# IO_BOARD_TOP.net
KiCad netlist of a schematic drawn in EAGLE
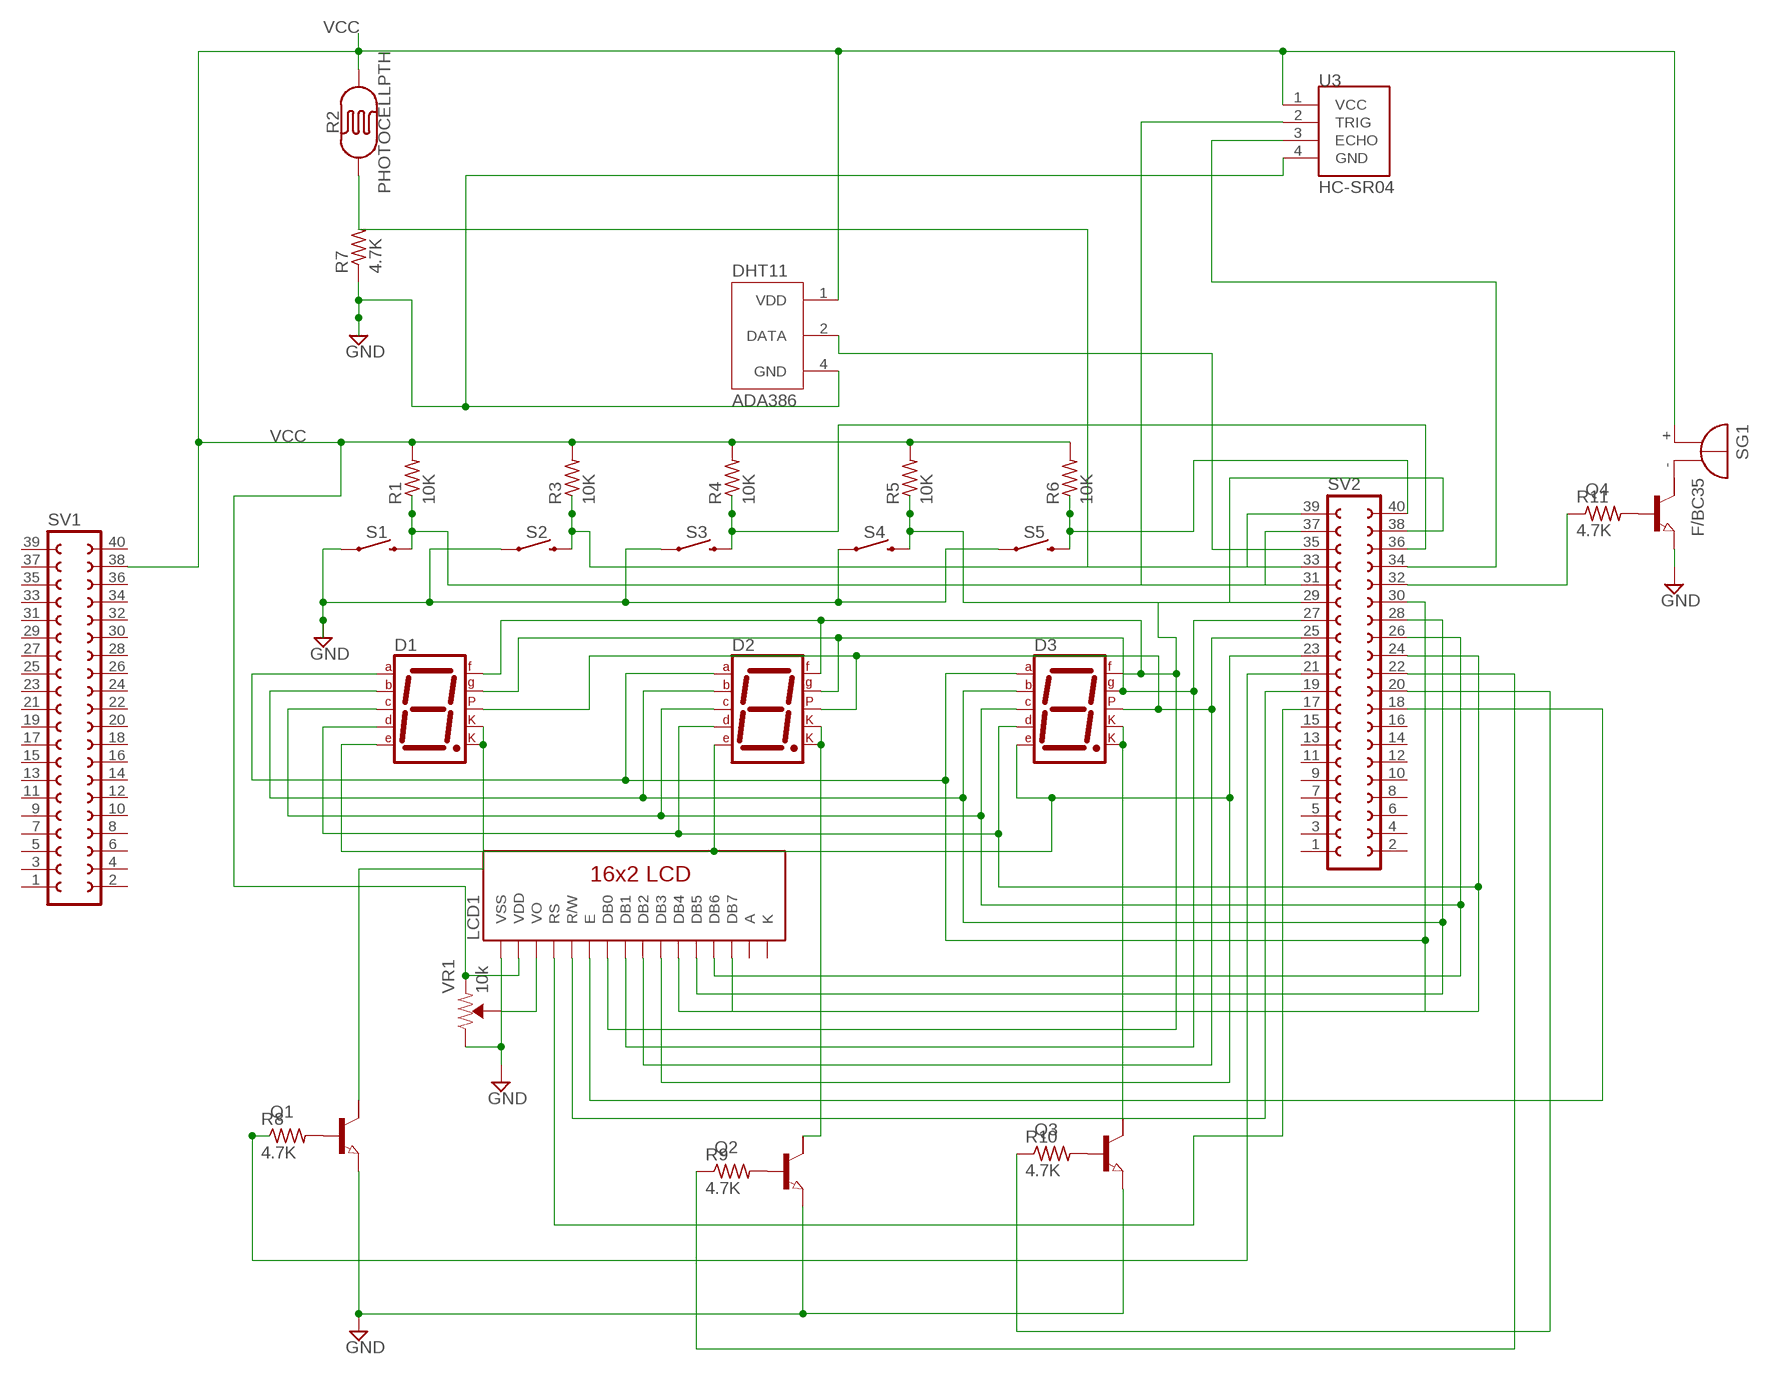
[diagram p0: schematic, sheet 1]

(export (version "E")
  (design (tool "Eeschema 10.0.6"))
  (components
    (comp (ref "D1")
      (value "7SEG-CK")
      (footprint "eagle-import:7SEG-13")
      (libsource (lib "eagle-import") (part "7SEG-CK"))
    )
    (comp (ref "D2")
      (value "7SEG-CK")
      (footprint "eagle-import:7SEG-13")
      (libsource (lib "eagle-import") (part "7SEG-CK"))
    )
    (comp (ref "D3")
      (value "7SEG-CK")
      (footprint "eagle-import:7SEG-13")
      (libsource (lib "eagle-import") (part "7SEG-CK"))
    )
    (comp (ref "DHT11")
      (value "ADA386")
      (footprint "eagle-import:XDCR_ADA386")
      (fields (field (name "MF") "Adafruit Industries"))
      (libsource (lib "eagle-import") (part "ADA386"))
    )
    (comp (ref "LCD1")
      (value "LCD-16X2SILK")
      (footprint "eagle-import:LCD-16X2")
      (libsource (lib "eagle-import") (part "LCD-16X2SILK"))
    )
    (comp (ref "Q1")
      (value "NPN-TRANSISTIOR-2COLSOT89")
      (footprint "eagle-import:SOT89")
      (libsource (lib "eagle-import") (part "NPN-TRANSISTIOR-2COLSOT89"))
    )
    (comp (ref "Q2")
      (value "NPN-TRANSISTIOR-2COLSOT89")
      (footprint "eagle-import:SOT89")
      (libsource (lib "eagle-import") (part "NPN-TRANSISTIOR-2COLSOT89"))
    )
    (comp (ref "Q3")
      (value "NPN-TRANSISTIOR-2COLSOT89")
      (footprint "eagle-import:SOT89")
      (libsource (lib "eagle-import") (part "NPN-TRANSISTIOR-2COLSOT89"))
    )
    (comp (ref "Q4")
      (value "NPN-TRANSISTIOR-2COLSOT89")
      (footprint "eagle-import:SOT89")
      (libsource (lib "eagle-import") (part "NPN-TRANSISTIOR-2COLSOT89"))
    )
    (comp (ref "R1")
      (value "10K")
      (footprint "eagle-import:0204V")
      (libsource (lib "eagle-import") (part "R-US_0204/2V"))
    )
    (comp (ref "R2")
      (value "PHOTOCELLPTH")
      (footprint "eagle-import:PHOTOCELL")
      (libsource (lib "eagle-import") (part "PHOTOCELLPTH"))
    )
    (comp (ref "R3")
      (value "10K")
      (footprint "eagle-import:0204V")
      (libsource (lib "eagle-import") (part "R-US_0204/2V"))
    )
    (comp (ref "R4")
      (value "10K")
      (footprint "eagle-import:0204V")
      (libsource (lib "eagle-import") (part "R-US_0204/2V"))
    )
    (comp (ref "R5")
      (value "10K")
      (footprint "eagle-import:0204V")
      (libsource (lib "eagle-import") (part "R-US_0204/2V"))
    )
    (comp (ref "R6")
      (value "10K")
      (footprint "eagle-import:0204V")
      (libsource (lib "eagle-import") (part "R-US_0204/2V"))
    )
    (comp (ref "R7")
      (value "4.7K")
      (footprint "eagle-import:0204V")
      (libsource (lib "eagle-import") (part "R-US_0204/2V"))
    )
    (comp (ref "R8")
      (value "4.7K")
      (footprint "eagle-import:0204V")
      (libsource (lib "eagle-import") (part "R-US_0204/2V"))
    )
    (comp (ref "R9")
      (value "4.7K")
      (footprint "eagle-import:0204V")
      (libsource (lib "eagle-import") (part "R-US_0204/2V"))
    )
    (comp (ref "R10")
      (value "4.7K")
      (footprint "eagle-import:0204V")
      (libsource (lib "eagle-import") (part "R-US_0204/2V"))
    )
    (comp (ref "R11")
      (value "4.7K")
      (footprint "eagle-import:0204V")
      (libsource (lib "eagle-import") (part "R-US_0204/2V"))
    )
    (comp (ref "S1")
      (value "MOMENTARY-SWITCH-SPST-SMD-4.6X2.8MM")
      (footprint "eagle-import:TACTILE_SWITCH_SMD_4.6X2.8MM")
      (libsource (lib "eagle-import") (part "MOMENTARY-SWITCH-SPST-SMD-4.6X2.8MM"))
    )
    (comp (ref "S2")
      (value "MOMENTARY-SWITCH-SPST-SMD-4.6X2.8MM")
      (footprint "eagle-import:TACTILE_SWITCH_SMD_4.6X2.8MM")
      (libsource (lib "eagle-import") (part "MOMENTARY-SWITCH-SPST-SMD-4.6X2.8MM"))
    )
    (comp (ref "S3")
      (value "MOMENTARY-SWITCH-SPST-SMD-4.6X2.8MM")
      (footprint "eagle-import:TACTILE_SWITCH_SMD_4.6X2.8MM")
      (libsource (lib "eagle-import") (part "MOMENTARY-SWITCH-SPST-SMD-4.6X2.8MM"))
    )
    (comp (ref "S4")
      (value "MOMENTARY-SWITCH-SPST-SMD-4.6X2.8MM")
      (footprint "eagle-import:TACTILE_SWITCH_SMD_4.6X2.8MM")
      (libsource (lib "eagle-import") (part "MOMENTARY-SWITCH-SPST-SMD-4.6X2.8MM"))
    )
    (comp (ref "S5")
      (value "MOMENTARY-SWITCH-SPST-SMD-5.2-REDUNDANT")
      (footprint "eagle-import:TACTILE_SWITCH_SMD_5.2MM")
      (libsource (lib "eagle-import") (part "MOMENTARY-SWITCH-SPST-SMD-5.2-REDUNDANT"))
    )
    (comp (ref "SG1")
      (value "F/BC35")
      (footprint "eagle-import:F_BC35")
      (libsource (lib "eagle-import") (part "F/BC35"))
    )
    (comp (ref "SV1")
      (value "FE20-2")
      (footprint "eagle-import:FE20-2")
      (libsource (lib "eagle-import") (part "FE20-2"))
    )
    (comp (ref "SV2")
      (value "FE20-2")
      (footprint "eagle-import:FE20-2")
      (libsource (lib "eagle-import") (part "FE20-2"))
    )
    (comp (ref "U3")
      (value "HC-SR04")
      (footprint "eagle-import:XCVR_HC-SR04")
      (fields (field (name "MF") "OSEPP Electronics LTD"))
      (libsource (lib "eagle-import") (part "HC-SR04"))
    )
    (comp (ref "VR1")
      (value "10k")
      (footprint "eagle-import:TRIMPOT-SMD-TC33X")
      (libsource (lib "eagle-import") (part "TRIMPOT-SMD-3MM-OPEN-1/10W-25%"))
    )
  )
  (nets
    (net (code "1") (name "/A") (class "Default")
      (node (ref "LCD1") (pin "15") (pinfunction "A_15") (pintype "power_in"))
    )
    (net (code "2") (name "/K") (class "Default")
      (node (ref "LCD1") (pin "16") (pinfunction "K_16") (pintype "power_in"))
    )
    (net (code "3") (name "/VCC") (class "Default")
      (node (ref "DHT11") (pin "1") (pinfunction "VDD_1") (pintype "power_in"))
      (node (ref "LCD1") (pin "2") (pinfunction "VDD_2") (pintype "power_in"))
      (node (ref "R1") (pin "2") (pinfunction "2_2") (pintype "passive"))
      (node (ref "R2") (pin "2") (pinfunction "P$2_2") (pintype "bidirectional"))
      (node (ref "R3") (pin "2") (pinfunction "2_2") (pintype "passive"))
      (node (ref "R4") (pin "2") (pinfunction "2_2") (pintype "passive"))
      (node (ref "R5") (pin "2") (pinfunction "2_2") (pintype "passive"))
      (node (ref "R6") (pin "2") (pinfunction "2_2") (pintype "passive"))
      (node (ref "SG1") (pin "+") (pinfunction "+_+") (pintype "passive"))
      (node (ref "SV1") (pin "38") (pinfunction "38_38") (pintype "passive"))
      (node (ref "U3") (pin "1") (pinfunction "VCC_1") (pintype "power_in"))
      (node (ref "VR1") (pin "3") (pinfunction "CCW_3") (pintype "passive"))
    )
    (net (code "4") (name "GND") (class "Default")
      (node (ref "DHT11") (pin "4") (pinfunction "GND_4") (pintype "power_in"))
      (node (ref "LCD1") (pin "1") (pinfunction "VSS_1") (pintype "power_in"))
      (node (ref "Q1") (pin "3") (pinfunction "E_3") (pintype "passive"))
      (node (ref "Q2") (pin "3") (pinfunction "E_3") (pintype "passive"))
      (node (ref "Q3") (pin "3") (pinfunction "E_3") (pintype "passive"))
      (node (ref "Q4") (pin "3") (pinfunction "E_3") (pintype "passive"))
      (node (ref "R7") (pin "1") (pinfunction "1_1") (pintype "passive"))
      (node (ref "S1") (pin "1") (pinfunction "1_1") (pintype "passive"))
      (node (ref "S1") (pin "2") (pinfunction "1_2") (pintype "passive"))
      (node (ref "S2") (pin "1") (pinfunction "1_1") (pintype "passive"))
      (node (ref "S2") (pin "2") (pinfunction "1_2") (pintype "passive"))
      (node (ref "S3") (pin "1") (pinfunction "1_1") (pintype "passive"))
      (node (ref "S3") (pin "2") (pinfunction "1_2") (pintype "passive"))
      (node (ref "S4") (pin "1") (pinfunction "1_1") (pintype "passive"))
      (node (ref "S4") (pin "2") (pinfunction "1_2") (pintype "passive"))
      (node (ref "S5") (pin "1") (pinfunction "1_1") (pintype "passive"))
      (node (ref "S5") (pin "2") (pinfunction "1_2") (pintype "passive"))
      (node (ref "U3") (pin "4") (pinfunction "GND_4") (pintype "power_in"))
      (node (ref "VR1") (pin "1") (pinfunction "CW_1") (pintype "passive"))
    )
    (net (code "5") (name "Net-(D1-A)") (class "Default")
      (node (ref "D1") (pin "7") (pinfunction "A_7") (pintype "passive"))
      (node (ref "D2") (pin "7") (pinfunction "A_7") (pintype "passive"))
      (node (ref "D3") (pin "7") (pinfunction "A_7") (pintype "passive"))
      (node (ref "LCD1") (pin "11") (pinfunction "DB4_11") (pintype "bidirectional"))
      (node (ref "SV2") (pin "30") (pinfunction "30_30") (pintype "passive"))
    )
    (net (code "6") (name "Net-(D1-B)") (class "Default")
      (node (ref "D1") (pin "6") (pinfunction "B_6") (pintype "passive"))
      (node (ref "D2") (pin "6") (pinfunction "B_6") (pintype "passive"))
      (node (ref "D3") (pin "6") (pinfunction "B_6") (pintype "passive"))
      (node (ref "LCD1") (pin "12") (pinfunction "DB5_12") (pintype "bidirectional"))
      (node (ref "SV2") (pin "28") (pinfunction "28_28") (pintype "passive"))
    )
    (net (code "7") (name "Net-(D1-C)") (class "Default")
      (node (ref "D1") (pin "4") (pinfunction "C_4") (pintype "passive"))
      (node (ref "D2") (pin "4") (pinfunction "C_4") (pintype "passive"))
      (node (ref "D3") (pin "4") (pinfunction "C_4") (pintype "passive"))
      (node (ref "LCD1") (pin "13") (pinfunction "DB6_13") (pintype "bidirectional"))
      (node (ref "SV2") (pin "26") (pinfunction "26_26") (pintype "passive"))
    )
    (net (code "8") (name "Net-(D1-CK1)") (class "Default")
      (node (ref "D1") (pin "3") (pinfunction "CK1_3") (pintype "passive"))
      (node (ref "D1") (pin "8") (pinfunction "CK2_8") (pintype "passive"))
      (node (ref "Q1") (pin "2") (pinfunction "C_2") (pintype "passive"))
    )
    (net (code "9") (name "Net-(D1-D)") (class "Default")
      (node (ref "D1") (pin "2") (pinfunction "D_2") (pintype "passive"))
      (node (ref "D2") (pin "2") (pinfunction "D_2") (pintype "passive"))
      (node (ref "D3") (pin "2") (pinfunction "D_2") (pintype "passive"))
      (node (ref "LCD1") (pin "14") (pinfunction "DB7_14") (pintype "bidirectional"))
      (node (ref "SV2") (pin "24") (pinfunction "24_24") (pintype "passive"))
    )
    (net (code "10") (name "Net-(D1-DP)") (class "Default")
      (node (ref "D1") (pin "5") (pinfunction "DP_5") (pintype "passive"))
      (node (ref "D2") (pin "5") (pinfunction "DP_5") (pintype "passive"))
      (node (ref "D3") (pin "5") (pinfunction "DP_5") (pintype "passive"))
      (node (ref "LCD1") (pin "9") (pinfunction "DB2_9") (pintype "bidirectional"))
      (node (ref "SV2") (pin "25") (pinfunction "25_25") (pintype "passive"))
    )
    (net (code "11") (name "Net-(D1-E)") (class "Default")
      (node (ref "D1") (pin "1") (pinfunction "E_1") (pintype "passive"))
      (node (ref "D2") (pin "1") (pinfunction "E_1") (pintype "passive"))
      (node (ref "D3") (pin "1") (pinfunction "E_1") (pintype "passive"))
      (node (ref "LCD1") (pin "10") (pinfunction "DB3_10") (pintype "bidirectional"))
      (node (ref "SV2") (pin "23") (pinfunction "23_23") (pintype "passive"))
    )
    (net (code "12") (name "Net-(D1-F)") (class "Default")
      (node (ref "D1") (pin "9") (pinfunction "F_9") (pintype "passive"))
      (node (ref "D2") (pin "9") (pinfunction "F_9") (pintype "passive"))
      (node (ref "D3") (pin "9") (pinfunction "F_9") (pintype "passive"))
      (node (ref "LCD1") (pin "7") (pinfunction "DB0_7") (pintype "bidirectional"))
      (node (ref "SV2") (pin "29") (pinfunction "29_29") (pintype "passive"))
    )
    (net (code "13") (name "Net-(D1-G)") (class "Default")
      (node (ref "D1") (pin "10") (pinfunction "G_10") (pintype "passive"))
      (node (ref "D2") (pin "10") (pinfunction "G_10") (pintype "passive"))
      (node (ref "D3") (pin "10") (pinfunction "G_10") (pintype "passive"))
      (node (ref "LCD1") (pin "8") (pinfunction "DB1_8") (pintype "bidirectional"))
      (node (ref "SV2") (pin "27") (pinfunction "27_27") (pintype "passive"))
    )
    (net (code "14") (name "Net-(D2-CK1)") (class "Default")
      (node (ref "D2") (pin "3") (pinfunction "CK1_3") (pintype "passive"))
      (node (ref "D2") (pin "8") (pinfunction "CK2_8") (pintype "passive"))
      (node (ref "Q2") (pin "2") (pinfunction "C_2") (pintype "passive"))
    )
    (net (code "15") (name "Net-(D3-CK1)") (class "Default")
      (node (ref "D3") (pin "3") (pinfunction "CK1_3") (pintype "passive"))
      (node (ref "D3") (pin "8") (pinfunction "CK2_8") (pintype "passive"))
      (node (ref "Q3") (pin "2") (pinfunction "C_2") (pintype "passive"))
    )
    (net (code "16") (name "Net-(DHT11-DATA)") (class "Default")
      (node (ref "DHT11") (pin "2") (pinfunction "DATA_2") (pintype "bidirectional"))
      (node (ref "SV2") (pin "35") (pinfunction "35_35") (pintype "passive"))
    )
    (net (code "17") (name "Net-(LCD1-E)") (class "Default")
      (node (ref "LCD1") (pin "6") (pinfunction "E_6") (pintype "input"))
      (node (ref "SV2") (pin "18") (pinfunction "18_18") (pintype "passive"))
    )
    (net (code "18") (name "Net-(LCD1-RS)") (class "Default")
      (node (ref "LCD1") (pin "4") (pinfunction "RS_4") (pintype "input"))
      (node (ref "SV2") (pin "17") (pinfunction "17_17") (pintype "passive"))
    )
    (net (code "19") (name "Net-(LCD1-R{slash}W)") (class "Default")
      (node (ref "LCD1") (pin "5") (pinfunction "R/W_5") (pintype "input"))
      (node (ref "SV2") (pin "19") (pinfunction "19_19") (pintype "passive"))
    )
    (net (code "20") (name "Net-(LCD1-VO)") (class "Default")
      (node (ref "LCD1") (pin "3") (pinfunction "VO_3") (pintype "bidirectional"))
      (node (ref "VR1") (pin "2") (pinfunction "WIPER_2") (pintype "passive"))
    )
    (net (code "21") (name "Net-(Q1-B)") (class "Default")
      (node (ref "Q1") (pin "1") (pinfunction "B_1") (pintype "passive"))
      (node (ref "R8") (pin "2") (pinfunction "2_2") (pintype "passive"))
    )
    (net (code "22") (name "Net-(Q2-B)") (class "Default")
      (node (ref "Q2") (pin "1") (pinfunction "B_1") (pintype "passive"))
      (node (ref "R9") (pin "2") (pinfunction "2_2") (pintype "passive"))
    )
    (net (code "23") (name "Net-(Q3-B)") (class "Default")
      (node (ref "Q3") (pin "1") (pinfunction "B_1") (pintype "passive"))
      (node (ref "R10") (pin "2") (pinfunction "2_2") (pintype "passive"))
    )
    (net (code "24") (name "Net-(Q4-B)") (class "Default")
      (node (ref "Q4") (pin "1") (pinfunction "B_1") (pintype "passive"))
      (node (ref "R11") (pin "2") (pinfunction "2_2") (pintype "passive"))
    )
    (net (code "25") (name "Net-(Q4-C)") (class "Default")
      (node (ref "Q4") (pin "2") (pinfunction "C_2") (pintype "passive"))
      (node (ref "SG1") (pin "-") (pinfunction "-_-") (pintype "passive"))
    )
    (net (code "26") (name "Net-(R1-Pad1)") (class "Default")
      (node (ref "R1") (pin "1") (pinfunction "1_1") (pintype "passive"))
      (node (ref "S1") (pin "3") (pinfunction "2_3") (pintype "passive"))
      (node (ref "S1") (pin "4") (pinfunction "2_4") (pintype "passive"))
      (node (ref "SV2") (pin "37") (pinfunction "37_37") (pintype "passive"))
    )
    (net (code "27") (name "Net-(R2-P$1)") (class "Default")
      (node (ref "R2") (pin "1") (pinfunction "P$1_1") (pintype "bidirectional"))
      (node (ref "R7") (pin "2") (pinfunction "2_2") (pintype "passive"))
      (node (ref "SV2") (pin "33") (pinfunction "33_33") (pintype "passive"))
    )
    (net (code "28") (name "Net-(R3-Pad1)") (class "Default")
      (node (ref "R3") (pin "1") (pinfunction "1_1") (pintype "passive"))
      (node (ref "S2") (pin "3") (pinfunction "2_3") (pintype "passive"))
      (node (ref "S2") (pin "4") (pinfunction "2_4") (pintype "passive"))
      (node (ref "SV2") (pin "39") (pinfunction "39_39") (pintype "passive"))
    )
    (net (code "29") (name "Net-(R4-Pad1)") (class "Default")
      (node (ref "R4") (pin "1") (pinfunction "1_1") (pintype "passive"))
      (node (ref "S3") (pin "3") (pinfunction "2_3") (pintype "passive"))
      (node (ref "S3") (pin "4") (pinfunction "2_4") (pintype "passive"))
      (node (ref "SV2") (pin "36") (pinfunction "36_36") (pintype "passive"))
    )
    (net (code "30") (name "Net-(R5-Pad1)") (class "Default")
      (node (ref "R5") (pin "1") (pinfunction "1_1") (pintype "passive"))
      (node (ref "S4") (pin "3") (pinfunction "2_3") (pintype "passive"))
      (node (ref "S4") (pin "4") (pinfunction "2_4") (pintype "passive"))
      (node (ref "SV2") (pin "38") (pinfunction "38_38") (pintype "passive"))
    )
    (net (code "31") (name "Net-(R6-Pad1)") (class "Default")
      (node (ref "R6") (pin "1") (pinfunction "1_1") (pintype "passive"))
      (node (ref "S5") (pin "3") (pinfunction "2_3") (pintype "passive"))
      (node (ref "S5") (pin "4") (pinfunction "2_4") (pintype "passive"))
      (node (ref "SV2") (pin "40") (pinfunction "40_40") (pintype "passive"))
    )
    (net (code "32") (name "Net-(R8-Pad1)") (class "Default")
      (node (ref "R8") (pin "1") (pinfunction "1_1") (pintype "passive"))
      (node (ref "SV2") (pin "21") (pinfunction "21_21") (pintype "passive"))
    )
    (net (code "33") (name "Net-(R9-Pad1)") (class "Default")
      (node (ref "R9") (pin "1") (pinfunction "1_1") (pintype "passive"))
      (node (ref "SV2") (pin "22") (pinfunction "22_22") (pintype "passive"))
    )
    (net (code "34") (name "Net-(R10-Pad1)") (class "Default")
      (node (ref "R10") (pin "1") (pinfunction "1_1") (pintype "passive"))
      (node (ref "SV2") (pin "20") (pinfunction "20_20") (pintype "passive"))
    )
    (net (code "35") (name "Net-(R11-Pad1)") (class "Default")
      (node (ref "R11") (pin "1") (pinfunction "1_1") (pintype "passive"))
      (node (ref "SV2") (pin "32") (pinfunction "32_32") (pintype "passive"))
    )
    (net (code "36") (name "Net-(U3-ECHO)") (class "Default")
      (node (ref "SV2") (pin "34") (pinfunction "34_34") (pintype "passive"))
      (node (ref "U3") (pin "3") (pinfunction "ECHO_3") (pintype "bidirectional"))
    )
    (net (code "37") (name "Net-(U3-TRIG)") (class "Default")
      (node (ref "SV2") (pin "31") (pinfunction "31_31") (pintype "passive"))
      (node (ref "U3") (pin "2") (pinfunction "TRIG_2") (pintype "bidirectional"))
    )
    (net (code "38") (name "unconnected-(Q1-C{slash}-Pad2@1)") (class "Default")
      (node (ref "Q1") (pin "2@1") (pinfunction "C/_2@1") (pintype "passive"))
    )
    (net (code "39") (name "unconnected-(Q2-C{slash}-Pad2@1)") (class "Default")
      (node (ref "Q2") (pin "2@1") (pinfunction "C/_2@1") (pintype "passive"))
    )
    (net (code "40") (name "unconnected-(Q3-C{slash}-Pad2@1)") (class "Default")
      (node (ref "Q3") (pin "2@1") (pinfunction "C/_2@1") (pintype "passive"))
    )
    (net (code "41") (name "unconnected-(Q4-C{slash}-Pad2@1)") (class "Default")
      (node (ref "Q4") (pin "2@1") (pinfunction "C/_2@1") (pintype "passive"))
    )
    (net (code "42") (name "unconnected-(SV1-Pad1)") (class "Default")
      (node (ref "SV1") (pin "1") (pinfunction "1_1") (pintype "passive"))
    )
    (net (code "43") (name "unconnected-(SV1-Pad2)") (class "Default")
      (node (ref "SV1") (pin "2") (pinfunction "2_2") (pintype "passive"))
    )
    (net (code "44") (name "unconnected-(SV1-Pad3)") (class "Default")
      (node (ref "SV1") (pin "3") (pinfunction "3_3") (pintype "passive"))
    )
    (net (code "45") (name "unconnected-(SV1-Pad4)") (class "Default")
      (node (ref "SV1") (pin "4") (pinfunction "4_4") (pintype "passive"))
    )
    (net (code "46") (name "unconnected-(SV1-Pad5)") (class "Default")
      (node (ref "SV1") (pin "5") (pinfunction "5_5") (pintype "passive"))
    )
    (net (code "47") (name "unconnected-(SV1-Pad6)") (class "Default")
      (node (ref "SV1") (pin "6") (pinfunction "6_6") (pintype "passive"))
    )
    (net (code "48") (name "unconnected-(SV1-Pad7)") (class "Default")
      (node (ref "SV1") (pin "7") (pinfunction "7_7") (pintype "passive"))
    )
    (net (code "49") (name "unconnected-(SV1-Pad8)") (class "Default")
      (node (ref "SV1") (pin "8") (pinfunction "8_8") (pintype "passive"))
    )
    (net (code "50") (name "unconnected-(SV1-Pad9)") (class "Default")
      (node (ref "SV1") (pin "9") (pinfunction "9_9") (pintype "passive"))
    )
    (net (code "51") (name "unconnected-(SV1-Pad10)") (class "Default")
      (node (ref "SV1") (pin "10") (pinfunction "10_10") (pintype "passive"))
    )
    (net (code "52") (name "unconnected-(SV1-Pad11)") (class "Default")
      (node (ref "SV1") (pin "11") (pinfunction "11_11") (pintype "passive"))
    )
    (net (code "53") (name "unconnected-(SV1-Pad12)") (class "Default")
      (node (ref "SV1") (pin "12") (pinfunction "12_12") (pintype "passive"))
    )
    (net (code "54") (name "unconnected-(SV1-Pad13)") (class "Default")
      (node (ref "SV1") (pin "13") (pinfunction "13_13") (pintype "passive"))
    )
    (net (code "55") (name "unconnected-(SV1-Pad14)") (class "Default")
      (node (ref "SV1") (pin "14") (pinfunction "14_14") (pintype "passive"))
    )
    (net (code "56") (name "unconnected-(SV1-Pad15)") (class "Default")
      (node (ref "SV1") (pin "15") (pinfunction "15_15") (pintype "passive"))
    )
    (net (code "57") (name "unconnected-(SV1-Pad16)") (class "Default")
      (node (ref "SV1") (pin "16") (pinfunction "16_16") (pintype "passive"))
    )
    (net (code "58") (name "unconnected-(SV1-Pad17)") (class "Default")
      (node (ref "SV1") (pin "17") (pinfunction "17_17") (pintype "passive"))
    )
    (net (code "59") (name "unconnected-(SV1-Pad18)") (class "Default")
      (node (ref "SV1") (pin "18") (pinfunction "18_18") (pintype "passive"))
    )
    (net (code "60") (name "unconnected-(SV1-Pad19)") (class "Default")
      (node (ref "SV1") (pin "19") (pinfunction "19_19") (pintype "passive"))
    )
    (net (code "61") (name "unconnected-(SV1-Pad20)") (class "Default")
      (node (ref "SV1") (pin "20") (pinfunction "20_20") (pintype "passive"))
    )
    (net (code "62") (name "unconnected-(SV1-Pad21)") (class "Default")
      (node (ref "SV1") (pin "21") (pinfunction "21_21") (pintype "passive"))
    )
    (net (code "63") (name "unconnected-(SV1-Pad22)") (class "Default")
      (node (ref "SV1") (pin "22") (pinfunction "22_22") (pintype "passive"))
    )
    (net (code "64") (name "unconnected-(SV1-Pad23)") (class "Default")
      (node (ref "SV1") (pin "23") (pinfunction "23_23") (pintype "passive"))
    )
    (net (code "65") (name "unconnected-(SV1-Pad24)") (class "Default")
      (node (ref "SV1") (pin "24") (pinfunction "24_24") (pintype "passive"))
    )
    (net (code "66") (name "unconnected-(SV1-Pad25)") (class "Default")
      (node (ref "SV1") (pin "25") (pinfunction "25_25") (pintype "passive"))
    )
    (net (code "67") (name "unconnected-(SV1-Pad26)") (class "Default")
      (node (ref "SV1") (pin "26") (pinfunction "26_26") (pintype "passive"))
    )
    (net (code "68") (name "unconnected-(SV1-Pad27)") (class "Default")
      (node (ref "SV1") (pin "27") (pinfunction "27_27") (pintype "passive"))
    )
    (net (code "69") (name "unconnected-(SV1-Pad28)") (class "Default")
      (node (ref "SV1") (pin "28") (pinfunction "28_28") (pintype "passive"))
    )
    (net (code "70") (name "unconnected-(SV1-Pad29)") (class "Default")
      (node (ref "SV1") (pin "29") (pinfunction "29_29") (pintype "passive"))
    )
    (net (code "71") (name "unconnected-(SV1-Pad30)") (class "Default")
      (node (ref "SV1") (pin "30") (pinfunction "30_30") (pintype "passive"))
    )
    (net (code "72") (name "unconnected-(SV1-Pad31)") (class "Default")
      (node (ref "SV1") (pin "31") (pinfunction "31_31") (pintype "passive"))
    )
    (net (code "73") (name "unconnected-(SV1-Pad32)") (class "Default")
      (node (ref "SV1") (pin "32") (pinfunction "32_32") (pintype "passive"))
    )
    (net (code "74") (name "unconnected-(SV1-Pad33)") (class "Default")
      (node (ref "SV1") (pin "33") (pinfunction "33_33") (pintype "passive"))
    )
    (net (code "75") (name "unconnected-(SV1-Pad34)") (class "Default")
      (node (ref "SV1") (pin "34") (pinfunction "34_34") (pintype "passive"))
    )
    (net (code "76") (name "unconnected-(SV1-Pad35)") (class "Default")
      (node (ref "SV1") (pin "35") (pinfunction "35_35") (pintype "passive"))
    )
    (net (code "77") (name "unconnected-(SV1-Pad36)") (class "Default")
      (node (ref "SV1") (pin "36") (pinfunction "36_36") (pintype "passive"))
    )
    (net (code "78") (name "unconnected-(SV1-Pad37)") (class "Default")
      (node (ref "SV1") (pin "37") (pinfunction "37_37") (pintype "passive"))
    )
    (net (code "79") (name "unconnected-(SV1-Pad39)") (class "Default")
      (node (ref "SV1") (pin "39") (pinfunction "39_39") (pintype "passive"))
    )
    (net (code "80") (name "unconnected-(SV1-Pad40)") (class "Default")
      (node (ref "SV1") (pin "40") (pinfunction "40_40") (pintype "passive"))
    )
    (net (code "81") (name "unconnected-(SV2-Pad1)") (class "Default")
      (node (ref "SV2") (pin "1") (pinfunction "1_1") (pintype "passive"))
    )
    (net (code "82") (name "unconnected-(SV2-Pad2)") (class "Default")
      (node (ref "SV2") (pin "2") (pinfunction "2_2") (pintype "passive"))
    )
    (net (code "83") (name "unconnected-(SV2-Pad3)") (class "Default")
      (node (ref "SV2") (pin "3") (pinfunction "3_3") (pintype "passive"))
    )
    (net (code "84") (name "unconnected-(SV2-Pad4)") (class "Default")
      (node (ref "SV2") (pin "4") (pinfunction "4_4") (pintype "passive"))
    )
    (net (code "85") (name "unconnected-(SV2-Pad5)") (class "Default")
      (node (ref "SV2") (pin "5") (pinfunction "5_5") (pintype "passive"))
    )
    (net (code "86") (name "unconnected-(SV2-Pad6)") (class "Default")
      (node (ref "SV2") (pin "6") (pinfunction "6_6") (pintype "passive"))
    )
    (net (code "87") (name "unconnected-(SV2-Pad7)") (class "Default")
      (node (ref "SV2") (pin "7") (pinfunction "7_7") (pintype "passive"))
    )
    (net (code "88") (name "unconnected-(SV2-Pad8)") (class "Default")
      (node (ref "SV2") (pin "8") (pinfunction "8_8") (pintype "passive"))
    )
    (net (code "89") (name "unconnected-(SV2-Pad9)") (class "Default")
      (node (ref "SV2") (pin "9") (pinfunction "9_9") (pintype "passive"))
    )
    (net (code "90") (name "unconnected-(SV2-Pad10)") (class "Default")
      (node (ref "SV2") (pin "10") (pinfunction "10_10") (pintype "passive"))
    )
    (net (code "91") (name "unconnected-(SV2-Pad11)") (class "Default")
      (node (ref "SV2") (pin "11") (pinfunction "11_11") (pintype "passive"))
    )
    (net (code "92") (name "unconnected-(SV2-Pad12)") (class "Default")
      (node (ref "SV2") (pin "12") (pinfunction "12_12") (pintype "passive"))
    )
    (net (code "93") (name "unconnected-(SV2-Pad13)") (class "Default")
      (node (ref "SV2") (pin "13") (pinfunction "13_13") (pintype "passive"))
    )
    (net (code "94") (name "unconnected-(SV2-Pad14)") (class "Default")
      (node (ref "SV2") (pin "14") (pinfunction "14_14") (pintype "passive"))
    )
    (net (code "95") (name "unconnected-(SV2-Pad15)") (class "Default")
      (node (ref "SV2") (pin "15") (pinfunction "15_15") (pintype "passive"))
    )
    (net (code "96") (name "unconnected-(SV2-Pad16)") (class "Default")
      (node (ref "SV2") (pin "16") (pinfunction "16_16") (pintype "passive"))
    )
  )
)
